# FlexPiece.net
KiCad netlist of a schematic drawn in EAGLE
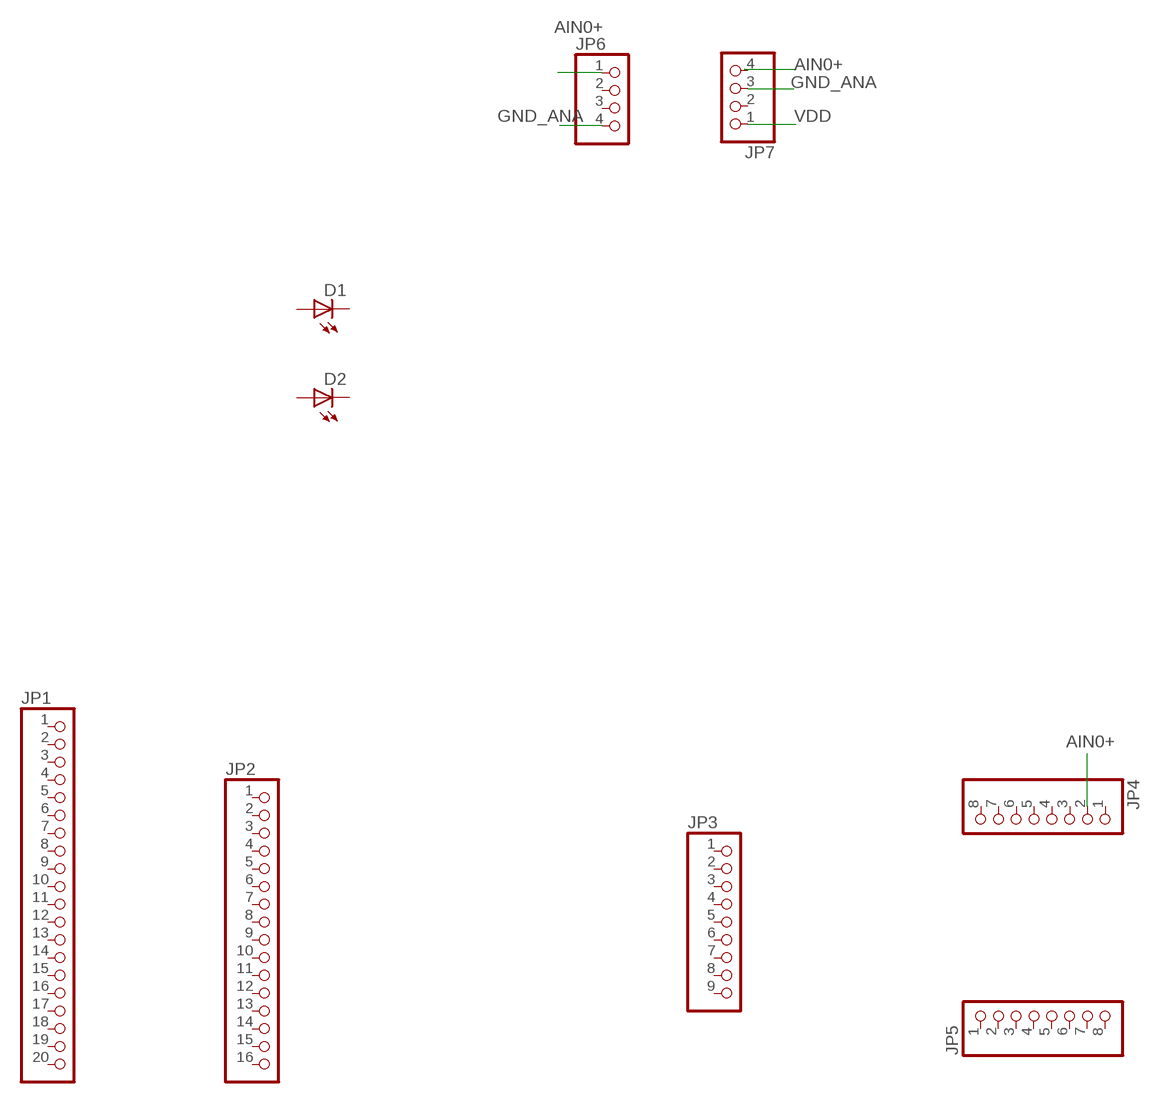
[diagram p0: schematic, sheet 1]

(export (version "E")
  (design (tool "Eeschema 10.0.6"))
  (components
    (comp (ref "D1")
      (value "LED1206")
      (footprint "eagle-import:LED-1206")
      (libsource (lib "eagle-import") (part "LED1206"))
    )
    (comp (ref "D2")
      (value "LED1206")
      (footprint "eagle-import:LED-1206")
      (libsource (lib "eagle-import") (part "LED1206"))
    )
    (comp (ref "JP1")
      (value "PINHD-1X20")
      (footprint "eagle-import:1X20")
      (libsource (lib "eagle-import") (part "PINHD-1X20"))
    )
    (comp (ref "JP2")
      (value "PINHD-1X16")
      (footprint "eagle-import:1X16")
      (libsource (lib "eagle-import") (part "PINHD-1X16"))
    )
    (comp (ref "JP3")
      (value "PINHD-1X9")
      (footprint "eagle-import:1X09")
      (libsource (lib "eagle-import") (part "PINHD-1X9"))
    )
    (comp (ref "JP4")
      (value "PINHD-1X8")
      (footprint "eagle-import:1X08")
      (libsource (lib "eagle-import") (part "PINHD-1X8"))
    )
    (comp (ref "JP5")
      (value "PINHD-1X8")
      (footprint "eagle-import:1X08")
      (libsource (lib "eagle-import") (part "PINHD-1X8"))
    )
    (comp (ref "JP6")
      (value "PINHD-1X4")
      (footprint "eagle-import:1X04")
      (libsource (lib "eagle-import") (part "PINHD-1X4"))
    )
    (comp (ref "JP7")
      (value "PINHD-1X4")
      (footprint "eagle-import:1X04")
      (libsource (lib "eagle-import") (part "PINHD-1X4"))
    )
  )
  (nets
    (net (code "1") (name "/AIN0+") (class "Default")
      (node (ref "JP4") (pin "2") (pinfunction "2_2") (pintype "passive"))
      (node (ref "JP6") (pin "1") (pinfunction "1_1") (pintype "passive"))
      (node (ref "JP7") (pin "4") (pinfunction "4_4") (pintype "passive"))
    )
    (net (code "2") (name "/GND_ANA") (class "Default")
      (node (ref "JP6") (pin "4") (pinfunction "4_4") (pintype "passive"))
      (node (ref "JP7") (pin "3") (pinfunction "3_3") (pintype "passive"))
    )
    (net (code "3") (name "/VDD") (class "Default")
      (node (ref "JP7") (pin "1") (pinfunction "1_1") (pintype "passive"))
    )
    (net (code "4") (name "unconnected-(D1-PadA)") (class "Default")
      (node (ref "D1") (pin "A") (pinfunction "A_A") (pintype "passive"))
    )
    (net (code "5") (name "unconnected-(D1-PadC)") (class "Default")
      (node (ref "D1") (pin "C") (pinfunction "C_C") (pintype "passive"))
    )
    (net (code "6") (name "unconnected-(D2-PadA)") (class "Default")
      (node (ref "D2") (pin "A") (pinfunction "A_A") (pintype "passive"))
    )
    (net (code "7") (name "unconnected-(D2-PadC)") (class "Default")
      (node (ref "D2") (pin "C") (pinfunction "C_C") (pintype "passive"))
    )
    (net (code "8") (name "unconnected-(JP1-Pad1)") (class "Default")
      (node (ref "JP1") (pin "1") (pinfunction "1_1") (pintype "passive"))
    )
    (net (code "9") (name "unconnected-(JP1-Pad2)") (class "Default")
      (node (ref "JP1") (pin "2") (pinfunction "2_2") (pintype "passive"))
    )
    (net (code "10") (name "unconnected-(JP1-Pad3)") (class "Default")
      (node (ref "JP1") (pin "3") (pinfunction "3_3") (pintype "passive"))
    )
    (net (code "11") (name "unconnected-(JP1-Pad4)") (class "Default")
      (node (ref "JP1") (pin "4") (pinfunction "4_4") (pintype "passive"))
    )
    (net (code "12") (name "unconnected-(JP1-Pad5)") (class "Default")
      (node (ref "JP1") (pin "5") (pinfunction "5_5") (pintype "passive"))
    )
    (net (code "13") (name "unconnected-(JP1-Pad6)") (class "Default")
      (node (ref "JP1") (pin "6") (pinfunction "6_6") (pintype "passive"))
    )
    (net (code "14") (name "unconnected-(JP1-Pad7)") (class "Default")
      (node (ref "JP1") (pin "7") (pinfunction "7_7") (pintype "passive"))
    )
    (net (code "15") (name "unconnected-(JP1-Pad8)") (class "Default")
      (node (ref "JP1") (pin "8") (pinfunction "8_8") (pintype "passive"))
    )
    (net (code "16") (name "unconnected-(JP1-Pad9)") (class "Default")
      (node (ref "JP1") (pin "9") (pinfunction "9_9") (pintype "passive"))
    )
    (net (code "17") (name "unconnected-(JP1-Pad10)") (class "Default")
      (node (ref "JP1") (pin "10") (pinfunction "10_10") (pintype "passive"))
    )
    (net (code "18") (name "unconnected-(JP1-Pad11)") (class "Default")
      (node (ref "JP1") (pin "11") (pinfunction "11_11") (pintype "passive"))
    )
    (net (code "19") (name "unconnected-(JP1-Pad12)") (class "Default")
      (node (ref "JP1") (pin "12") (pinfunction "12_12") (pintype "passive"))
    )
    (net (code "20") (name "unconnected-(JP1-Pad13)") (class "Default")
      (node (ref "JP1") (pin "13") (pinfunction "13_13") (pintype "passive"))
    )
    (net (code "21") (name "unconnected-(JP1-Pad14)") (class "Default")
      (node (ref "JP1") (pin "14") (pinfunction "14_14") (pintype "passive"))
    )
    (net (code "22") (name "unconnected-(JP1-Pad15)") (class "Default")
      (node (ref "JP1") (pin "15") (pinfunction "15_15") (pintype "passive"))
    )
    (net (code "23") (name "unconnected-(JP1-Pad16)") (class "Default")
      (node (ref "JP1") (pin "16") (pinfunction "16_16") (pintype "passive"))
    )
    (net (code "24") (name "unconnected-(JP1-Pad17)") (class "Default")
      (node (ref "JP1") (pin "17") (pinfunction "17_17") (pintype "passive"))
    )
    (net (code "25") (name "unconnected-(JP1-Pad18)") (class "Default")
      (node (ref "JP1") (pin "18") (pinfunction "18_18") (pintype "passive"))
    )
    (net (code "26") (name "unconnected-(JP1-Pad19)") (class "Default")
      (node (ref "JP1") (pin "19") (pinfunction "19_19") (pintype "passive"))
    )
    (net (code "27") (name "unconnected-(JP1-Pad20)") (class "Default")
      (node (ref "JP1") (pin "20") (pinfunction "20_20") (pintype "passive"))
    )
    (net (code "28") (name "unconnected-(JP2-Pad1)") (class "Default")
      (node (ref "JP2") (pin "1") (pinfunction "1_1") (pintype "passive"))
    )
    (net (code "29") (name "unconnected-(JP2-Pad2)") (class "Default")
      (node (ref "JP2") (pin "2") (pinfunction "2_2") (pintype "passive"))
    )
    (net (code "30") (name "unconnected-(JP2-Pad3)") (class "Default")
      (node (ref "JP2") (pin "3") (pinfunction "3_3") (pintype "passive"))
    )
    (net (code "31") (name "unconnected-(JP2-Pad4)") (class "Default")
      (node (ref "JP2") (pin "4") (pinfunction "4_4") (pintype "passive"))
    )
    (net (code "32") (name "unconnected-(JP2-Pad5)") (class "Default")
      (node (ref "JP2") (pin "5") (pinfunction "5_5") (pintype "passive"))
    )
    (net (code "33") (name "unconnected-(JP2-Pad6)") (class "Default")
      (node (ref "JP2") (pin "6") (pinfunction "6_6") (pintype "passive"))
    )
    (net (code "34") (name "unconnected-(JP2-Pad7)") (class "Default")
      (node (ref "JP2") (pin "7") (pinfunction "7_7") (pintype "passive"))
    )
    (net (code "35") (name "unconnected-(JP2-Pad8)") (class "Default")
      (node (ref "JP2") (pin "8") (pinfunction "8_8") (pintype "passive"))
    )
    (net (code "36") (name "unconnected-(JP2-Pad9)") (class "Default")
      (node (ref "JP2") (pin "9") (pinfunction "9_9") (pintype "passive"))
    )
    (net (code "37") (name "unconnected-(JP2-Pad10)") (class "Default")
      (node (ref "JP2") (pin "10") (pinfunction "10_10") (pintype "passive"))
    )
    (net (code "38") (name "unconnected-(JP2-Pad11)") (class "Default")
      (node (ref "JP2") (pin "11") (pinfunction "11_11") (pintype "passive"))
    )
    (net (code "39") (name "unconnected-(JP2-Pad12)") (class "Default")
      (node (ref "JP2") (pin "12") (pinfunction "12_12") (pintype "passive"))
    )
    (net (code "40") (name "unconnected-(JP2-Pad13)") (class "Default")
      (node (ref "JP2") (pin "13") (pinfunction "13_13") (pintype "passive"))
    )
    (net (code "41") (name "unconnected-(JP2-Pad14)") (class "Default")
      (node (ref "JP2") (pin "14") (pinfunction "14_14") (pintype "passive"))
    )
    (net (code "42") (name "unconnected-(JP2-Pad15)") (class "Default")
      (node (ref "JP2") (pin "15") (pinfunction "15_15") (pintype "passive"))
    )
    (net (code "43") (name "unconnected-(JP2-Pad16)") (class "Default")
      (node (ref "JP2") (pin "16") (pinfunction "16_16") (pintype "passive"))
    )
    (net (code "44") (name "unconnected-(JP3-Pad1)") (class "Default")
      (node (ref "JP3") (pin "1") (pinfunction "1_1") (pintype "passive"))
    )
    (net (code "45") (name "unconnected-(JP3-Pad2)") (class "Default")
      (node (ref "JP3") (pin "2") (pinfunction "2_2") (pintype "passive"))
    )
    (net (code "46") (name "unconnected-(JP3-Pad3)") (class "Default")
      (node (ref "JP3") (pin "3") (pinfunction "3_3") (pintype "passive"))
    )
    (net (code "47") (name "unconnected-(JP3-Pad4)") (class "Default")
      (node (ref "JP3") (pin "4") (pinfunction "4_4") (pintype "passive"))
    )
    (net (code "48") (name "unconnected-(JP3-Pad5)") (class "Default")
      (node (ref "JP3") (pin "5") (pinfunction "5_5") (pintype "passive"))
    )
    (net (code "49") (name "unconnected-(JP3-Pad6)") (class "Default")
      (node (ref "JP3") (pin "6") (pinfunction "6_6") (pintype "passive"))
    )
    (net (code "50") (name "unconnected-(JP3-Pad7)") (class "Default")
      (node (ref "JP3") (pin "7") (pinfunction "7_7") (pintype "passive"))
    )
    (net (code "51") (name "unconnected-(JP3-Pad8)") (class "Default")
      (node (ref "JP3") (pin "8") (pinfunction "8_8") (pintype "passive"))
    )
    (net (code "52") (name "unconnected-(JP3-Pad9)") (class "Default")
      (node (ref "JP3") (pin "9") (pinfunction "9_9") (pintype "passive"))
    )
    (net (code "53") (name "unconnected-(JP4-Pad1)") (class "Default")
      (node (ref "JP4") (pin "1") (pinfunction "1_1") (pintype "passive"))
    )
    (net (code "54") (name "unconnected-(JP4-Pad3)") (class "Default")
      (node (ref "JP4") (pin "3") (pinfunction "3_3") (pintype "passive"))
    )
    (net (code "55") (name "unconnected-(JP4-Pad4)") (class "Default")
      (node (ref "JP4") (pin "4") (pinfunction "4_4") (pintype "passive"))
    )
    (net (code "56") (name "unconnected-(JP4-Pad5)") (class "Default")
      (node (ref "JP4") (pin "5") (pinfunction "5_5") (pintype "passive"))
    )
    (net (code "57") (name "unconnected-(JP4-Pad6)") (class "Default")
      (node (ref "JP4") (pin "6") (pinfunction "6_6") (pintype "passive"))
    )
    (net (code "58") (name "unconnected-(JP4-Pad7)") (class "Default")
      (node (ref "JP4") (pin "7") (pinfunction "7_7") (pintype "passive"))
    )
    (net (code "59") (name "unconnected-(JP4-Pad8)") (class "Default")
      (node (ref "JP4") (pin "8") (pinfunction "8_8") (pintype "passive"))
    )
    (net (code "60") (name "unconnected-(JP5-Pad1)") (class "Default")
      (node (ref "JP5") (pin "1") (pinfunction "1_1") (pintype "passive"))
    )
    (net (code "61") (name "unconnected-(JP5-Pad2)") (class "Default")
      (node (ref "JP5") (pin "2") (pinfunction "2_2") (pintype "passive"))
    )
    (net (code "62") (name "unconnected-(JP5-Pad3)") (class "Default")
      (node (ref "JP5") (pin "3") (pinfunction "3_3") (pintype "passive"))
    )
    (net (code "63") (name "unconnected-(JP5-Pad4)") (class "Default")
      (node (ref "JP5") (pin "4") (pinfunction "4_4") (pintype "passive"))
    )
    (net (code "64") (name "unconnected-(JP5-Pad5)") (class "Default")
      (node (ref "JP5") (pin "5") (pinfunction "5_5") (pintype "passive"))
    )
    (net (code "65") (name "unconnected-(JP5-Pad6)") (class "Default")
      (node (ref "JP5") (pin "6") (pinfunction "6_6") (pintype "passive"))
    )
    (net (code "66") (name "unconnected-(JP5-Pad7)") (class "Default")
      (node (ref "JP5") (pin "7") (pinfunction "7_7") (pintype "passive"))
    )
    (net (code "67") (name "unconnected-(JP5-Pad8)") (class "Default")
      (node (ref "JP5") (pin "8") (pinfunction "8_8") (pintype "passive"))
    )
    (net (code "68") (name "unconnected-(JP6-Pad2)") (class "Default")
      (node (ref "JP6") (pin "2") (pinfunction "2_2") (pintype "passive"))
    )
    (net (code "69") (name "unconnected-(JP6-Pad3)") (class "Default")
      (node (ref "JP6") (pin "3") (pinfunction "3_3") (pintype "passive"))
    )
    (net (code "70") (name "unconnected-(JP7-Pad2)") (class "Default")
      (node (ref "JP7") (pin "2") (pinfunction "2_2") (pintype "passive"))
    )
  )
)
